# hwc.net
KiCad netlist of a schematic drawn in EAGLE
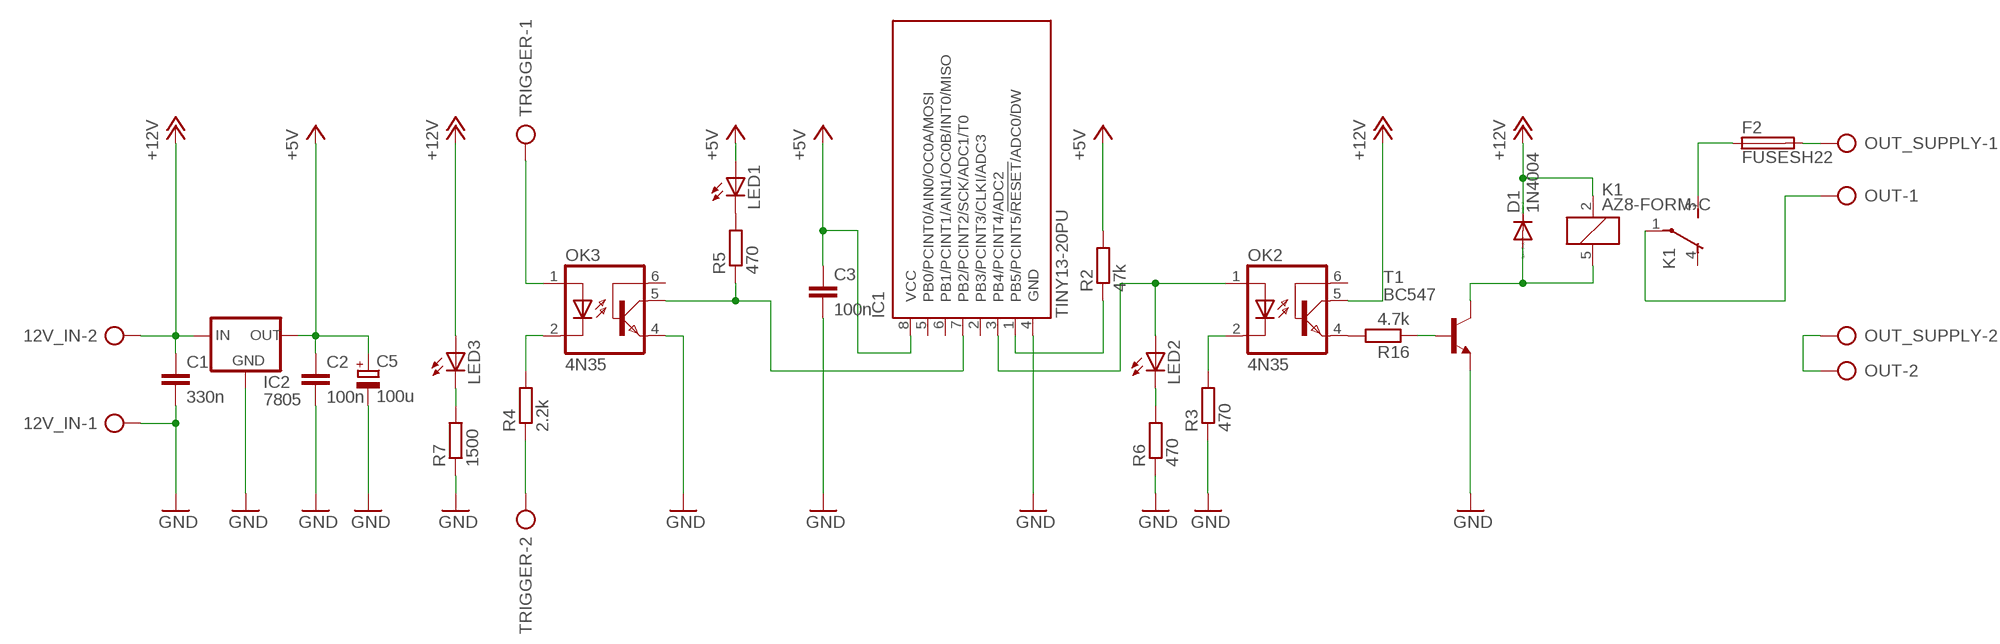
[diagram p0: schematic, sheet 1]

(export (version "E")
  (design (tool "Eeschema 10.0.6"))
  (components
    (comp (ref "12V_IN")
      (value "AK300/2")
      (footprint "eagle-import:AK300_2")
      (libsource (lib "eagle-import") (part "AK300/2"))
    )
    (comp (ref "C1")
      (value "330n")
      (footprint "eagle-import:C050-025X075")
      (libsource (lib "eagle-import") (part "C-EU050-025X075"))
    )
    (comp (ref "C2")
      (value "100n")
      (footprint "eagle-import:C050-025X075")
      (libsource (lib "eagle-import") (part "C-EU050-025X075"))
    )
    (comp (ref "C3")
      (value "100n")
      (footprint "eagle-import:C050-025X075")
      (libsource (lib "eagle-import") (part "C-EU050-025X075"))
    )
    (comp (ref "C5")
      (value "100u")
      (footprint "eagle-import:E5-8,5")
      (libsource (lib "eagle-import") (part "CPOL-EUE5-8.5"))
    )
    (comp (ref "D1")
      (value "1N4004")
      (footprint "eagle-import:DO41-10")
      (libsource (lib "eagle-import") (part "1N4004"))
    )
    (comp (ref "F2")
      (value "FUSESH22")
      (footprint "eagle-import:SH22")
      (libsource (lib "eagle-import") (part "FUSESH22"))
    )
    (comp (ref "IC1")
      (value "TINY13-20PU")
      (footprint "eagle-import:DIL08")
      (fields (field (name "MPN") "ATTINY13-20PU"))
      (libsource (lib "eagle-import") (part "TINY13PU-20"))
    )
    (comp (ref "IC2")
      (value "7805")
      (footprint "eagle-import:78XXL")
      (libsource (lib "eagle-import") (part "78XXL"))
    )
    (comp (ref "K1")
      (value "AZ8-FORM-C")
      (footprint "eagle-import:AZ8")
      (libsource (lib "eagle-import") (part "AZ8-FORM-C"))
    )
    (comp (ref "LED1")
      (value "LED5MM")
      (footprint "eagle-import:LED5MM")
      (libsource (lib "eagle-import") (part "LED5MM"))
    )
    (comp (ref "LED2")
      (value "LED5MM")
      (footprint "eagle-import:LED5MM")
      (libsource (lib "eagle-import") (part "LED5MM"))
    )
    (comp (ref "LED3")
      (value "LED5MM")
      (footprint "eagle-import:LED5MM")
      (libsource (lib "eagle-import") (part "LED5MM"))
    )
    (comp (ref "OK2")
      (value "4N35")
      (footprint "eagle-import:DIL06")
      (fields (field (name "MF") "FAIRCHILD SEMICONDUCTOR"))
      (libsource (lib "eagle-import") (part "4N35"))
    )
    (comp (ref "OK3")
      (value "4N35")
      (footprint "eagle-import:DIL06")
      (fields (field (name "MF") "FAIRCHILD SEMICONDUCTOR"))
      (libsource (lib "eagle-import") (part "4N35"))
    )
    (comp (ref "OUT")
      (value "AK300/2")
      (footprint "eagle-import:AK300_2")
      (libsource (lib "eagle-import") (part "AK300/2"))
    )
    (comp (ref "OUT_SUPPLY")
      (value "AK300/2")
      (footprint "eagle-import:AK300_2")
      (libsource (lib "eagle-import") (part "AK300/2"))
    )
    (comp (ref "R2")
      (value "47k")
      (footprint "eagle-import:0204_7")
      (libsource (lib "eagle-import") (part "R-EU_0204/7"))
    )
    (comp (ref "R3")
      (value "470")
      (footprint "eagle-import:0204_7")
      (libsource (lib "eagle-import") (part "R-EU_0204/7"))
    )
    (comp (ref "R4")
      (value "2.2k")
      (footprint "eagle-import:0204_7")
      (libsource (lib "eagle-import") (part "R-EU_0204/7"))
    )
    (comp (ref "R5")
      (value "470")
      (footprint "eagle-import:0204_7")
      (libsource (lib "eagle-import") (part "R-EU_0204/7"))
    )
    (comp (ref "R6")
      (value "470")
      (footprint "eagle-import:0204_7")
      (libsource (lib "eagle-import") (part "R-EU_0204/7"))
    )
    (comp (ref "R7")
      (value "1500")
      (footprint "eagle-import:0204_7")
      (libsource (lib "eagle-import") (part "R-EU_0204/7"))
    )
    (comp (ref "R16")
      (value "4.7k")
      (footprint "eagle-import:0204_7")
      (libsource (lib "eagle-import") (part "R-EU_0204/7"))
    )
    (comp (ref "T1")
      (value "BC547")
      (footprint "eagle-import:TO92")
      (libsource (lib "eagle-import") (part "BC547"))
    )
    (comp (ref "TRIGGER")
      (value "AK300/2")
      (footprint "eagle-import:AK300_2")
      (libsource (lib "eagle-import") (part "AK300/2"))
    )
  )
  (nets
    (net (code "1") (name "+5V") (class "Default")
      (node (ref "C2") (pin "1") (pinfunction "1_1") (pintype "passive"))
      (node (ref "C3") (pin "1") (pinfunction "1_1") (pintype "passive"))
      (node (ref "C5") (pin "+") (pinfunction "+_+") (pintype "passive"))
      (node (ref "IC1") (pin "8") (pinfunction "VCC_8") (pintype "power_in"))
      (node (ref "IC2") (pin "OUT") (pinfunction "OUT_OUT") (pintype "passive"))
      (node (ref "LED1") (pin "A") (pinfunction "A_A") (pintype "passive"))
      (node (ref "R2") (pin "2") (pinfunction "2_2") (pintype "passive"))
    )
    (net (code "2") (name "+12V") (class "Default")
      (node (ref "12V_IN") (pin "2") (pinfunction "KL_2") (pintype "passive"))
      (node (ref "C1") (pin "1") (pinfunction "1_1") (pintype "passive"))
      (node (ref "D1") (pin "C") (pinfunction "C_C") (pintype "passive"))
      (node (ref "IC2") (pin "IN") (pinfunction "IN_IN") (pintype "input"))
      (node (ref "K1") (pin "2") (pinfunction "1_2") (pintype "passive"))
      (node (ref "LED3") (pin "A") (pinfunction "A_A") (pintype "passive"))
      (node (ref "OK2") (pin "5") (pinfunction "COL_5") (pintype "passive"))
    )
    (net (code "3") (name "GND") (class "Default")
      (node (ref "12V_IN") (pin "1") (pinfunction "KL_1") (pintype "passive"))
      (node (ref "C1") (pin "2") (pinfunction "2_2") (pintype "passive"))
      (node (ref "C2") (pin "2") (pinfunction "2_2") (pintype "passive"))
      (node (ref "C3") (pin "2") (pinfunction "2_2") (pintype "passive"))
      (node (ref "C5") (pin "-") (pinfunction "-_-") (pintype "passive"))
      (node (ref "IC1") (pin "4") (pinfunction "GND_4") (pintype "power_in"))
      (node (ref "IC2") (pin "GND") (pinfunction "GND_GND") (pintype "input"))
      (node (ref "OK3") (pin "4") (pinfunction "EMI_4") (pintype "passive"))
      (node (ref "R3") (pin "1") (pinfunction "1_1") (pintype "passive"))
      (node (ref "R6") (pin "1") (pinfunction "1_1") (pintype "passive"))
      (node (ref "R7") (pin "1") (pinfunction "1_1") (pintype "passive"))
      (node (ref "T1") (pin "1") (pinfunction "E_1") (pintype "passive"))
    )
    (net (code "4") (name "Net-(IC1-PB2{slash}PCINT2{slash}SCK{slash}ADC1{slash}T0)") (class "Default")
      (node (ref "IC1") (pin "7") (pinfunction "PB2/PCINT2/SCK/ADC1/T0_7") (pintype "bidirectional"))
      (node (ref "OK3") (pin "5") (pinfunction "COL_5") (pintype "passive"))
      (node (ref "R5") (pin "1") (pinfunction "1_1") (pintype "passive"))
    )
    (net (code "5") (name "Net-(IC1-PB4{slash}PCINT4{slash}ADC2)") (class "Default")
      (node (ref "IC1") (pin "3") (pinfunction "PB4/PCINT4/ADC2_3") (pintype "bidirectional"))
      (node (ref "LED2") (pin "A") (pinfunction "A_A") (pintype "passive"))
      (node (ref "OK2") (pin "1") (pinfunction "A_1") (pintype "passive"))
    )
    (net (code "6") (name "Net-(IC1-PB5{slash}PCINT5{slash}~{RESET}{slash}ADC0{slash}DW)") (class "Default")
      (node (ref "IC1") (pin "1") (pinfunction "PB5/PCINT5/~{RESET}/ADC0/DW_1") (pintype "bidirectional"))
      (node (ref "R2") (pin "1") (pinfunction "1_1") (pintype "passive"))
    )
    (net (code "7") (name "Net-(K1A-P)") (class "Default")
      (node (ref "K1") (pin "1") (pinfunction "P_1") (pintype "passive"))
      (node (ref "OUT") (pin "1") (pinfunction "KL_1") (pintype "passive"))
    )
    (net (code "8") (name "Net-(K1A-S)") (class "Default")
      (node (ref "F2") (pin "1") (pinfunction "1_1") (pintype "passive"))
      (node (ref "K1") (pin "3") (pinfunction "S_3") (pintype "passive"))
    )
    (net (code "9") (name "Net-(K1B-2)") (class "Default")
      (node (ref "D1") (pin "A") (pinfunction "A_A") (pintype "passive"))
      (node (ref "K1") (pin "5") (pinfunction "2_5") (pintype "passive"))
      (node (ref "T1") (pin "3") (pinfunction "C_3") (pintype "passive"))
    )
    (net (code "10") (name "Net-(LED1-C)") (class "Default")
      (node (ref "LED1") (pin "K") (pinfunction "C_K") (pintype "passive"))
      (node (ref "R5") (pin "2") (pinfunction "2_2") (pintype "passive"))
    )
    (net (code "11") (name "Net-(LED2-C)") (class "Default")
      (node (ref "LED2") (pin "K") (pinfunction "C_K") (pintype "passive"))
      (node (ref "R6") (pin "2") (pinfunction "2_2") (pintype "passive"))
    )
    (net (code "12") (name "Net-(LED3-C)") (class "Default")
      (node (ref "LED3") (pin "K") (pinfunction "C_K") (pintype "passive"))
      (node (ref "R7") (pin "2") (pinfunction "2_2") (pintype "passive"))
    )
    (net (code "13") (name "Net-(OK2-C)") (class "Default")
      (node (ref "OK2") (pin "2") (pinfunction "C_2") (pintype "passive"))
      (node (ref "R3") (pin "2") (pinfunction "2_2") (pintype "passive"))
    )
    (net (code "14") (name "Net-(OK2-EMI)") (class "Default")
      (node (ref "OK2") (pin "4") (pinfunction "EMI_4") (pintype "passive"))
      (node (ref "R16") (pin "2") (pinfunction "2_2") (pintype "passive"))
    )
    (net (code "15") (name "Net-(OK3-A)") (class "Default")
      (node (ref "OK3") (pin "1") (pinfunction "A_1") (pintype "passive"))
      (node (ref "TRIGGER") (pin "1") (pinfunction "KL_1") (pintype "passive"))
    )
    (net (code "16") (name "Net-(OK3-C)") (class "Default")
      (node (ref "OK3") (pin "2") (pinfunction "C_2") (pintype "passive"))
      (node (ref "R4") (pin "2") (pinfunction "2_2") (pintype "passive"))
    )
    (net (code "17") (name "Net-(OUTB-KL)") (class "Default")
      (node (ref "OUT") (pin "2") (pinfunction "KL_2") (pintype "passive"))
      (node (ref "OUT_SUPPLY") (pin "2") (pinfunction "KL_2") (pintype "passive"))
    )
    (net (code "18") (name "Net-(OUT_SUPPLYA-KL)") (class "Default")
      (node (ref "F2") (pin "2") (pinfunction "2_2") (pintype "passive"))
      (node (ref "OUT_SUPPLY") (pin "1") (pinfunction "KL_1") (pintype "passive"))
    )
    (net (code "19") (name "Net-(T1-B)") (class "Default")
      (node (ref "R16") (pin "1") (pinfunction "1_1") (pintype "passive"))
      (node (ref "T1") (pin "2") (pinfunction "B_2") (pintype "passive"))
    )
    (net (code "20") (name "Net-(TRIGGERB-KL)") (class "Default")
      (node (ref "R4") (pin "1") (pinfunction "1_1") (pintype "passive"))
      (node (ref "TRIGGER") (pin "2") (pinfunction "KL_2") (pintype "passive"))
    )
    (net (code "21") (name "unconnected-(IC1-PB0{slash}PCINT0{slash}AIN0{slash}OC0A{slash}MOSI-Pad5)") (class "Default")
      (node (ref "IC1") (pin "5") (pinfunction "PB0/PCINT0/AIN0/OC0A/MOSI_5") (pintype "bidirectional"))
    )
    (net (code "22") (name "unconnected-(IC1-PB1{slash}PCINT1{slash}AIN1{slash}OC0B{slash}INT0{slash}MISO-Pad6)") (class "Default")
      (node (ref "IC1") (pin "6") (pinfunction "PB1/PCINT1/AIN1/OC0B/INT0/MISO_6") (pintype "bidirectional"))
    )
    (net (code "23") (name "unconnected-(IC1-PB3{slash}PCINT3{slash}CLKI{slash}ADC3-Pad2)") (class "Default")
      (node (ref "IC1") (pin "2") (pinfunction "PB3/PCINT3/CLKI/ADC3_2") (pintype "bidirectional"))
    )
    (net (code "24") (name "unconnected-(K1A-O-Pad4)") (class "Default")
      (node (ref "K1") (pin "4") (pinfunction "O_4") (pintype "passive"))
    )
    (net (code "25") (name "unconnected-(OK2-BAS-Pad6)") (class "Default")
      (node (ref "OK2") (pin "6") (pinfunction "BAS_6") (pintype "passive"))
    )
    (net (code "26") (name "unconnected-(OK3-BAS-Pad6)") (class "Default")
      (node (ref "OK3") (pin "6") (pinfunction "BAS_6") (pintype "passive"))
    )
  )
)
